# hdmi.net
KiCad netlist of a schematic drawn in EAGLE
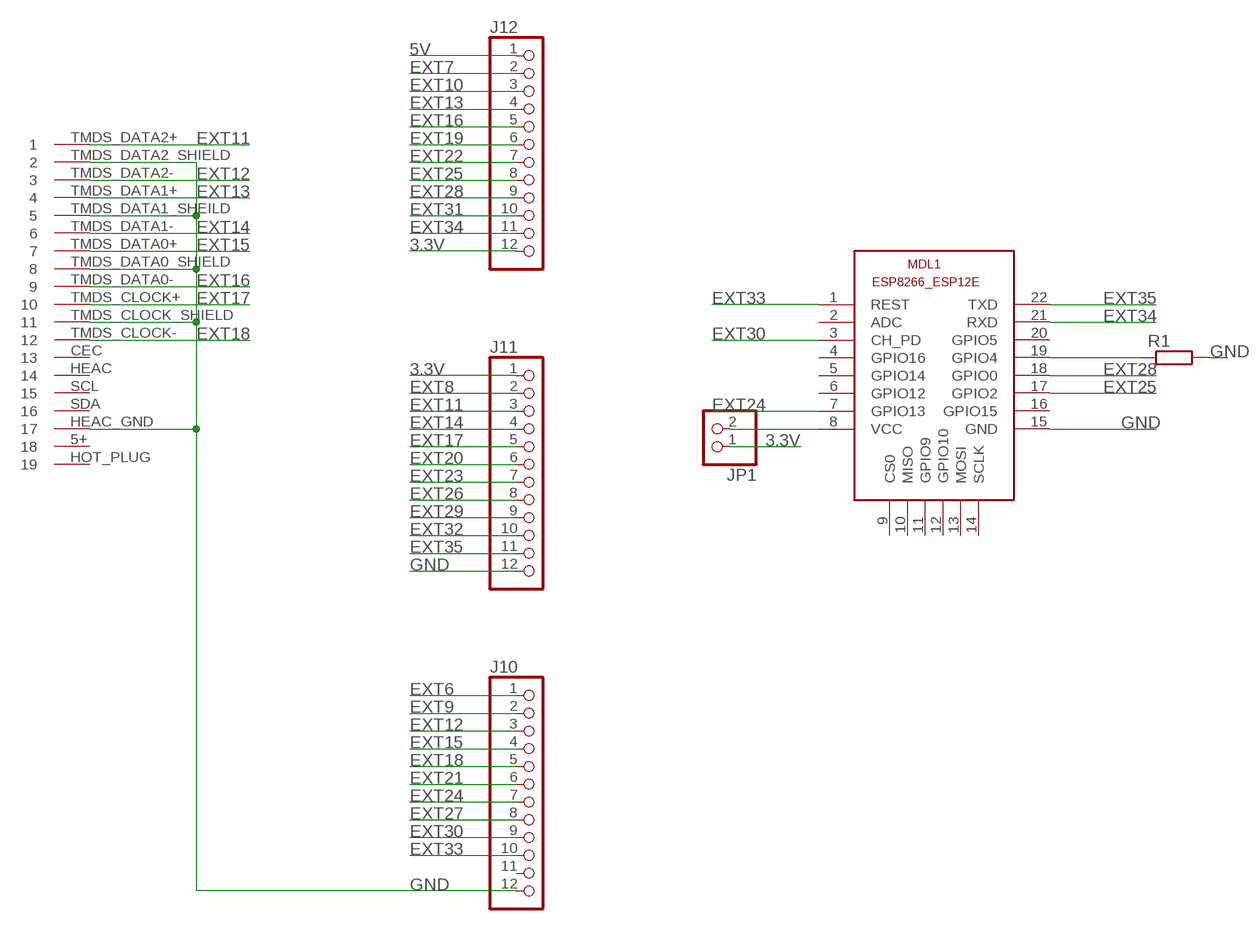
[diagram p0: schematic, sheet 1]

(export (version "E")
  (design (tool "Eeschema 10.0.6"))
  (components
    (comp (ref "J10")
      (value "PINHD-1X12")
      (footprint "eagle-import:1X12")
      (libsource (lib "eagle-import") (part "PINHD-1X12"))
    )
    (comp (ref "J11")
      (value "PINHD-1X12")
      (footprint "eagle-import:1X12")
      (libsource (lib "eagle-import") (part "PINHD-1X12"))
    )
    (comp (ref "J12")
      (value "PINHD-1X12")
      (footprint "eagle-import:1X12")
      (libsource (lib "eagle-import") (part "PINHD-1X12"))
    )
    (comp (ref "JP1")
      (value "PINHD-1X2/90")
      (footprint "eagle-import:1X02_90")
      (libsource (lib "eagle-import") (part "PINHD-1X2/90"))
    )
    (comp (ref "MDL1")
      (value "ESP8266-12EESP8266-ESP12E")
      (footprint "eagle-import:ESP8266-ESP12E")
      (libsource (lib "eagle-import") (part "ESP8266-12EESP8266-ESP12E"))
    )
    (comp (ref "R1")
      (value "R-EU_M0805")
      (footprint "eagle-import:M0805")
      (libsource (lib "eagle-import") (part "R-EU_M0805"))
    )
    (comp (ref "U$2")
      (value "HDMI")
      (footprint "eagle-import:DS1115")
      (libsource (lib "eagle-import") (part "HDMI"))
    )
  )
  (nets
    (net (code "1") (name "/3.3V") (class "Default")
      (node (ref "J11") (pin "1") (pinfunction "1_1") (pintype "passive"))
      (node (ref "J12") (pin "12") (pinfunction "12_12") (pintype "passive"))
      (node (ref "JP1") (pin "1") (pinfunction "1_1") (pintype "passive"))
    )
    (net (code "2") (name "/5V") (class "Default")
      (node (ref "J12") (pin "1") (pinfunction "1_1") (pintype "passive"))
    )
    (net (code "3") (name "/EXT6") (class "Default")
      (node (ref "J10") (pin "1") (pinfunction "1_1") (pintype "passive"))
    )
    (net (code "4") (name "/EXT7") (class "Default")
      (node (ref "J12") (pin "2") (pinfunction "2_2") (pintype "passive"))
    )
    (net (code "5") (name "/EXT8") (class "Default")
      (node (ref "J11") (pin "2") (pinfunction "2_2") (pintype "passive"))
    )
    (net (code "6") (name "/EXT9") (class "Default")
      (node (ref "J10") (pin "2") (pinfunction "2_2") (pintype "passive"))
    )
    (net (code "7") (name "/EXT10") (class "Default")
      (node (ref "J12") (pin "3") (pinfunction "3_3") (pintype "passive"))
    )
    (net (code "8") (name "/EXT11") (class "Default")
      (node (ref "J11") (pin "3") (pinfunction "3_3") (pintype "passive"))
      (node (ref "U$2") (pin "TMDS_DATA2+") (pinfunction "1_TMDS_DATA2+") (pintype "bidirectional"))
    )
    (net (code "9") (name "/EXT12") (class "Default")
      (node (ref "J10") (pin "3") (pinfunction "3_3") (pintype "passive"))
      (node (ref "U$2") (pin "TMDS_DATA2-") (pinfunction "3_TMDS_DATA2-") (pintype "bidirectional"))
    )
    (net (code "10") (name "/EXT13") (class "Default")
      (node (ref "J12") (pin "4") (pinfunction "4_4") (pintype "passive"))
      (node (ref "U$2") (pin "TMDS_DATA1+") (pinfunction "4_TMDS_DATA1+") (pintype "bidirectional"))
    )
    (net (code "11") (name "/EXT14") (class "Default")
      (node (ref "J11") (pin "4") (pinfunction "4_4") (pintype "passive"))
      (node (ref "U$2") (pin "TMDS_DATA1-") (pinfunction "6_TMDS_DATA1-") (pintype "bidirectional"))
    )
    (net (code "12") (name "/EXT15") (class "Default")
      (node (ref "J10") (pin "4") (pinfunction "4_4") (pintype "passive"))
      (node (ref "U$2") (pin "TMDS_DATA0+") (pinfunction "7_TMDS_DATA0+") (pintype "bidirectional"))
    )
    (net (code "13") (name "/EXT16") (class "Default")
      (node (ref "J12") (pin "5") (pinfunction "5_5") (pintype "passive"))
      (node (ref "U$2") (pin "TMDS_DATA0-") (pinfunction "9_TMDS_DATA0-") (pintype "bidirectional"))
    )
    (net (code "14") (name "/EXT17") (class "Default")
      (node (ref "J11") (pin "5") (pinfunction "5_5") (pintype "passive"))
      (node (ref "U$2") (pin "TMDS_CLOCK+") (pinfunction "10_TMDS_CLOCK+") (pintype "bidirectional"))
    )
    (net (code "15") (name "/EXT18") (class "Default")
      (node (ref "J10") (pin "5") (pinfunction "5_5") (pintype "passive"))
      (node (ref "U$2") (pin "TMDS_CLOCK-") (pinfunction "12_TMDS_CLOCK-") (pintype "bidirectional"))
    )
    (net (code "16") (name "/EXT19") (class "Default")
      (node (ref "J12") (pin "6") (pinfunction "6_6") (pintype "passive"))
    )
    (net (code "17") (name "/EXT20") (class "Default")
      (node (ref "J11") (pin "6") (pinfunction "6_6") (pintype "passive"))
    )
    (net (code "18") (name "/EXT21") (class "Default")
      (node (ref "J10") (pin "6") (pinfunction "6_6") (pintype "passive"))
    )
    (net (code "19") (name "/EXT22") (class "Default")
      (node (ref "J12") (pin "7") (pinfunction "7_7") (pintype "passive"))
    )
    (net (code "20") (name "/EXT23") (class "Default")
      (node (ref "J11") (pin "7") (pinfunction "7_7") (pintype "passive"))
    )
    (net (code "21") (name "/EXT24") (class "Default")
      (node (ref "J10") (pin "7") (pinfunction "7_7") (pintype "passive"))
      (node (ref "MDL1") (pin "7") (pinfunction "GPIO13_7") (pintype "bidirectional"))
    )
    (net (code "22") (name "/EXT25") (class "Default")
      (node (ref "J12") (pin "8") (pinfunction "8_8") (pintype "passive"))
      (node (ref "MDL1") (pin "17") (pinfunction "GPIO2_17") (pintype "bidirectional"))
    )
    (net (code "23") (name "/EXT26") (class "Default")
      (node (ref "J11") (pin "8") (pinfunction "8_8") (pintype "passive"))
    )
    (net (code "24") (name "/EXT27") (class "Default")
      (node (ref "J10") (pin "8") (pinfunction "8_8") (pintype "passive"))
    )
    (net (code "25") (name "/EXT28") (class "Default")
      (node (ref "J12") (pin "9") (pinfunction "9_9") (pintype "passive"))
      (node (ref "MDL1") (pin "18") (pinfunction "GPIO0_18") (pintype "bidirectional"))
    )
    (net (code "26") (name "/EXT29") (class "Default")
      (node (ref "J11") (pin "9") (pinfunction "9_9") (pintype "passive"))
    )
    (net (code "27") (name "/EXT30") (class "Default")
      (node (ref "J10") (pin "9") (pinfunction "9_9") (pintype "passive"))
      (node (ref "MDL1") (pin "3") (pinfunction "CH_PD_3") (pintype "bidirectional"))
    )
    (net (code "28") (name "/EXT31") (class "Default")
      (node (ref "J12") (pin "10") (pinfunction "10_10") (pintype "passive"))
    )
    (net (code "29") (name "/EXT32") (class "Default")
      (node (ref "J11") (pin "10") (pinfunction "10_10") (pintype "passive"))
    )
    (net (code "30") (name "/EXT33") (class "Default")
      (node (ref "J10") (pin "10") (pinfunction "10_10") (pintype "passive"))
      (node (ref "MDL1") (pin "1") (pinfunction "REST_1") (pintype "bidirectional"))
    )
    (net (code "31") (name "/EXT34") (class "Default")
      (node (ref "J12") (pin "11") (pinfunction "11_11") (pintype "passive"))
      (node (ref "MDL1") (pin "21") (pinfunction "RXD_21") (pintype "bidirectional"))
    )
    (net (code "32") (name "/EXT35") (class "Default")
      (node (ref "J11") (pin "11") (pinfunction "11_11") (pintype "passive"))
      (node (ref "MDL1") (pin "22") (pinfunction "TXD_22") (pintype "bidirectional"))
    )
    (net (code "33") (name "/GND") (class "Default")
      (node (ref "J10") (pin "12") (pinfunction "12_12") (pintype "passive"))
      (node (ref "J11") (pin "12") (pinfunction "12_12") (pintype "passive"))
      (node (ref "MDL1") (pin "15") (pinfunction "GND_15") (pintype "bidirectional"))
      (node (ref "R1") (pin "2") (pinfunction "2_2") (pintype "passive"))
      (node (ref "U$2") (pin "HEAC_GND") (pinfunction "17_HEAC_GND") (pintype "bidirectional"))
      (node (ref "U$2") (pin "TMDS_CLOCK_SHIELD") (pinfunction "11_TMDS_CLOCK_SHIELD") (pintype "bidirectional"))
      (node (ref "U$2") (pin "TMDS_DATA0_SHIELD") (pinfunction "8_TMDS_DATA0_SHIELD") (pintype "bidirectional"))
      (node (ref "U$2") (pin "TMDS_DATA1_SHEILD") (pinfunction "5_TMDS_DATA1_SHEILD") (pintype "bidirectional"))
      (node (ref "U$2") (pin "TMDS_DATA2_SHIELD") (pinfunction "2_TMDS_DATA2_SHIELD") (pintype "bidirectional"))
    )
    (net (code "34") (name "Net-(MDL1-GPIO4)") (class "Default")
      (node (ref "MDL1") (pin "19") (pinfunction "GPIO4_19") (pintype "bidirectional"))
      (node (ref "R1") (pin "1") (pinfunction "1_1") (pintype "passive"))
    )
    (net (code "35") (name "Net-(MDL1-VCC)") (class "Default")
      (node (ref "JP1") (pin "2") (pinfunction "2_2") (pintype "passive"))
      (node (ref "MDL1") (pin "8") (pinfunction "VCC_8") (pintype "bidirectional"))
    )
    (net (code "36") (name "unconnected-(J10-Pad11)") (class "Default")
      (node (ref "J10") (pin "11") (pinfunction "11_11") (pintype "passive"))
    )
    (net (code "37") (name "unconnected-(MDL1-ADC-Pad2)") (class "Default")
      (node (ref "MDL1") (pin "2") (pinfunction "ADC_2") (pintype "bidirectional"))
    )
    (net (code "38") (name "unconnected-(MDL1-CS0-Pad9)") (class "Default")
      (node (ref "MDL1") (pin "9") (pinfunction "CS0_9") (pintype "bidirectional"))
    )
    (net (code "39") (name "unconnected-(MDL1-GPIO5-Pad20)") (class "Default")
      (node (ref "MDL1") (pin "20") (pinfunction "GPIO5_20") (pintype "bidirectional"))
    )
    (net (code "40") (name "unconnected-(MDL1-GPIO9-Pad11)") (class "Default")
      (node (ref "MDL1") (pin "11") (pinfunction "GPIO9_11") (pintype "bidirectional"))
    )
    (net (code "41") (name "unconnected-(MDL1-GPIO10-Pad12)") (class "Default")
      (node (ref "MDL1") (pin "12") (pinfunction "GPIO10_12") (pintype "bidirectional"))
    )
    (net (code "42") (name "unconnected-(MDL1-GPIO12-Pad6)") (class "Default")
      (node (ref "MDL1") (pin "6") (pinfunction "GPIO12_6") (pintype "bidirectional"))
    )
    (net (code "43") (name "unconnected-(MDL1-GPIO14-Pad5)") (class "Default")
      (node (ref "MDL1") (pin "5") (pinfunction "GPIO14_5") (pintype "bidirectional"))
    )
    (net (code "44") (name "unconnected-(MDL1-GPIO15-Pad16)") (class "Default")
      (node (ref "MDL1") (pin "16") (pinfunction "GPIO15_16") (pintype "bidirectional"))
    )
    (net (code "45") (name "unconnected-(MDL1-GPIO16-Pad4)") (class "Default")
      (node (ref "MDL1") (pin "4") (pinfunction "GPIO16_4") (pintype "bidirectional"))
    )
    (net (code "46") (name "unconnected-(MDL1-MISO-Pad10)") (class "Default")
      (node (ref "MDL1") (pin "10") (pinfunction "MISO_10") (pintype "bidirectional"))
    )
    (net (code "47") (name "unconnected-(MDL1-MOSI-Pad13)") (class "Default")
      (node (ref "MDL1") (pin "13") (pinfunction "MOSI_13") (pintype "bidirectional"))
    )
    (net (code "48") (name "unconnected-(MDL1-SCLK-Pad14)") (class "Default")
      (node (ref "MDL1") (pin "14") (pinfunction "SCLK_14") (pintype "bidirectional"))
    )
    (net (code "49") (name "unconnected-(U$2-13-PadCEC)") (class "Default")
      (node (ref "U$2") (pin "CEC") (pinfunction "13_CEC") (pintype "bidirectional"))
    )
    (net (code "50") (name "unconnected-(U$2-14-PadHEAC)") (class "Default")
      (node (ref "U$2") (pin "HEAC") (pinfunction "14_HEAC") (pintype "bidirectional"))
    )
    (net (code "51") (name "unconnected-(U$2-15-PadSCL)") (class "Default")
      (node (ref "U$2") (pin "SCL") (pinfunction "15_SCL") (pintype "bidirectional"))
    )
    (net (code "52") (name "unconnected-(U$2-16-PadSDA)") (class "Default")
      (node (ref "U$2") (pin "SDA") (pinfunction "16_SDA") (pintype "bidirectional"))
    )
    (net (code "53") (name "unconnected-(U$2-18-Pad5+)") (class "Default")
      (node (ref "U$2") (pin "5+") (pinfunction "18_5+") (pintype "bidirectional"))
    )
    (net (code "54") (name "unconnected-(U$2-19-PadHOT_PLUG)") (class "Default")
      (node (ref "U$2") (pin "HOT_PLUG") (pinfunction "19_HOT_PLUG") (pintype "bidirectional"))
    )
  )
)
